# BKU.net
KiCad netlist of a schematic drawn in EAGLE
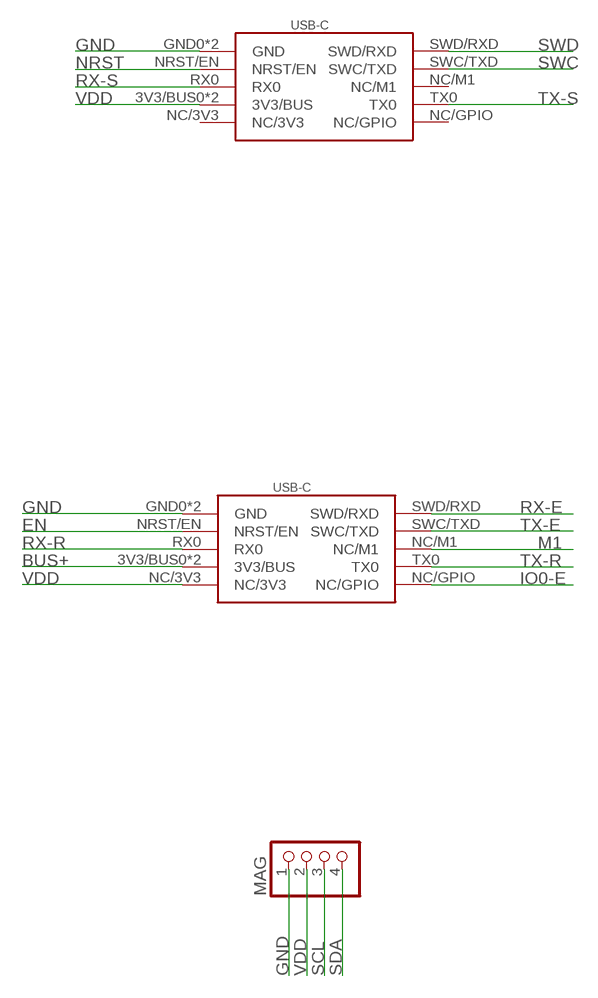
[diagram p0: schematic, sheet 1, part 1 of 2]
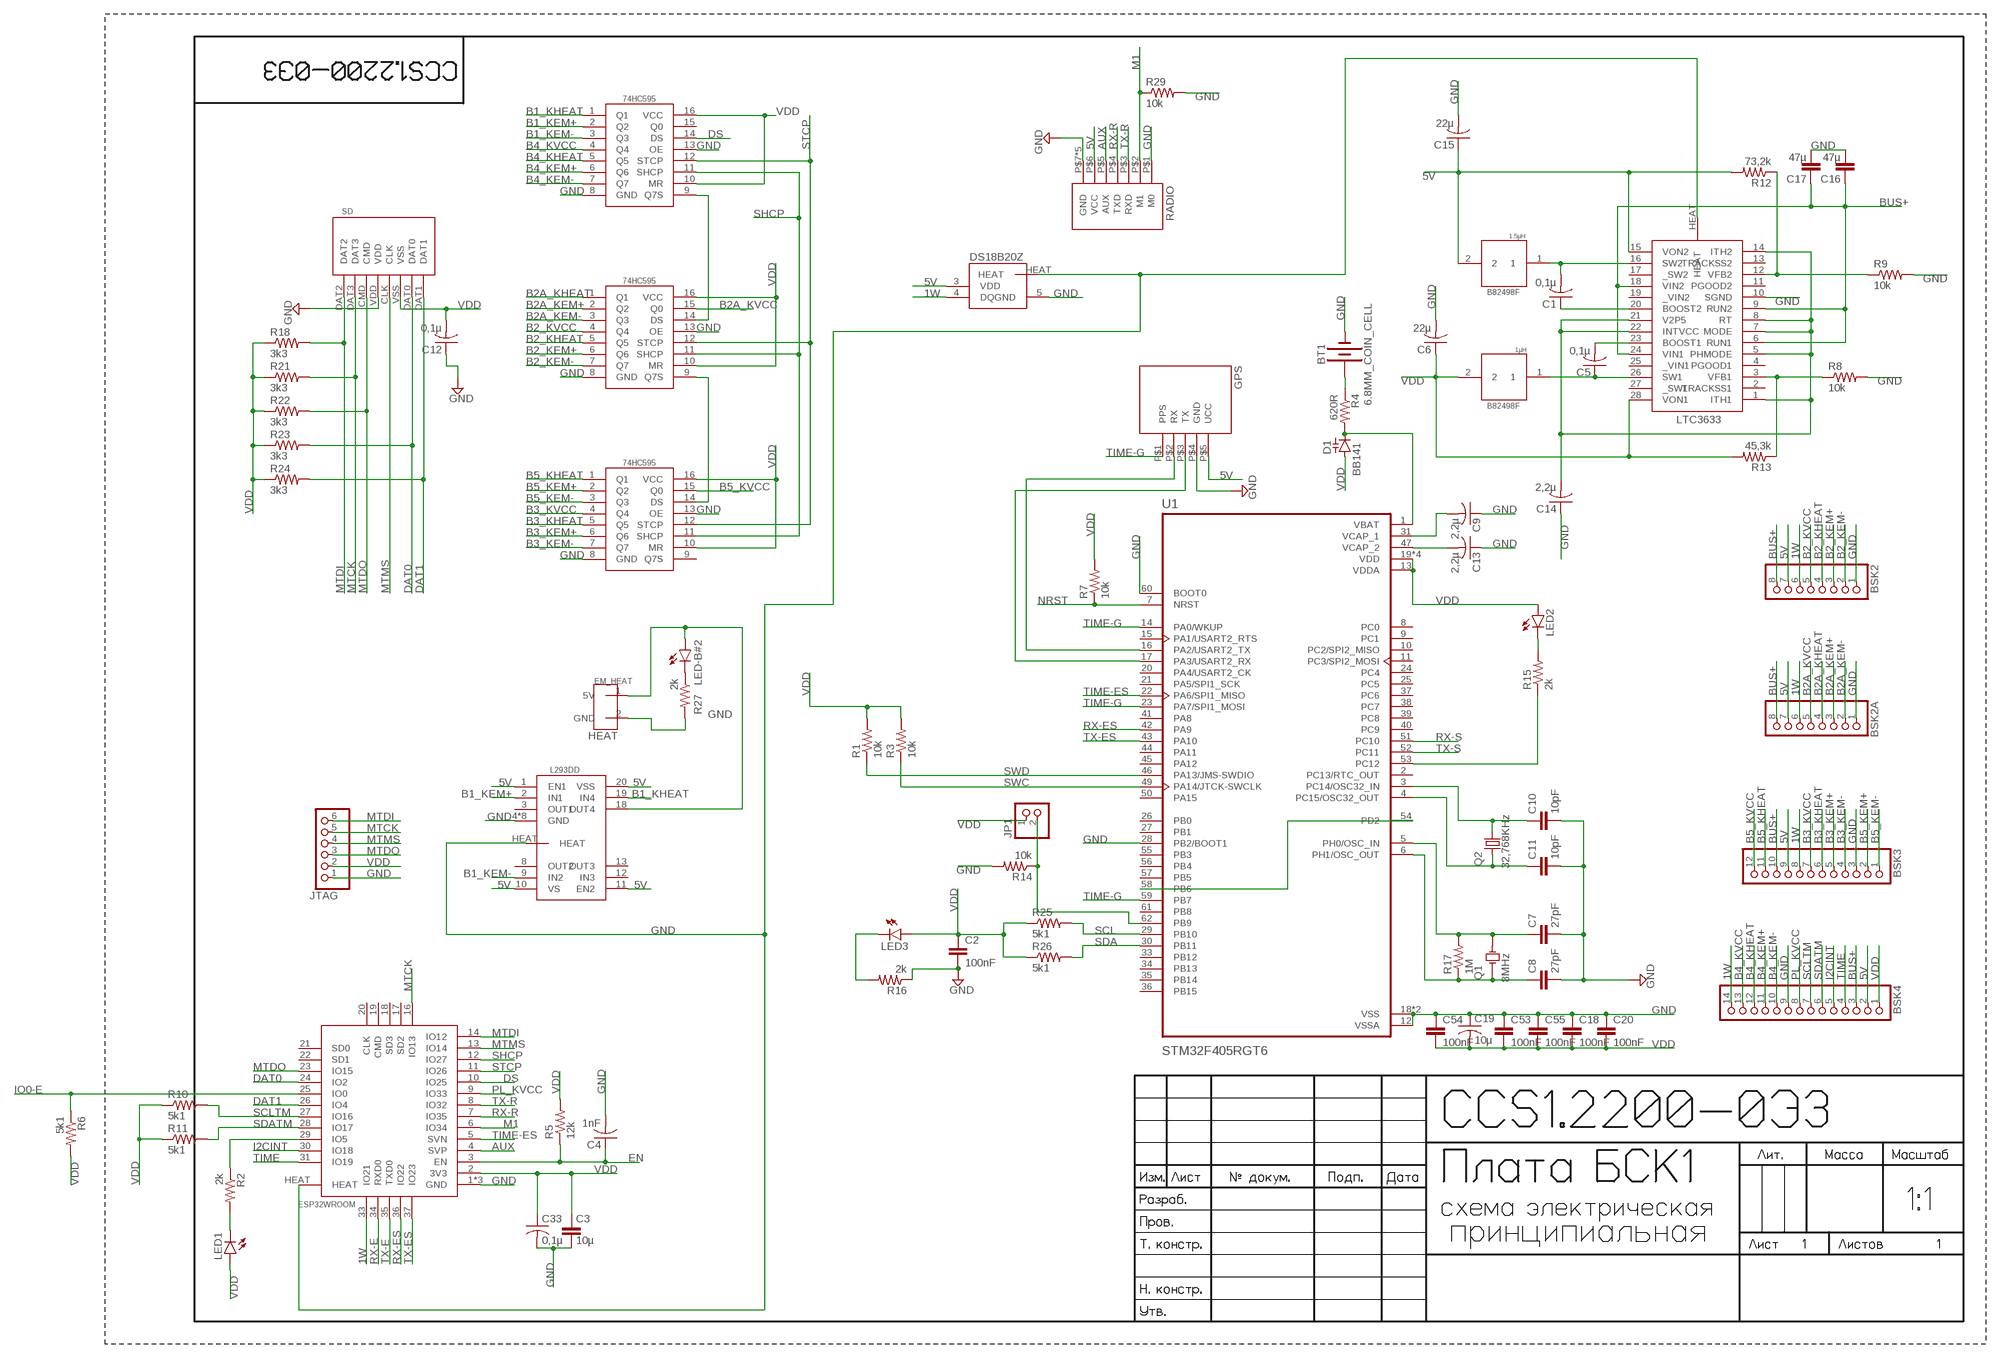
[diagram p1: schematic, sheet 1, part 2 of 2]

(export (version "E")
  (design (tool "Eeschema 10.0.6"))
  (components
    (comp (ref "BSK2")
      (value "PINHD-1X8")
      (footprint "eagle-import:1X08")
      (libsource (lib "eagle-import") (part "PINHD-1X8"))
    )
    (comp (ref "BSK2A")
      (value "PINHD-1X8")
      (footprint "eagle-import:1X08")
      (libsource (lib "eagle-import") (part "PINHD-1X8"))
    )
    (comp (ref "BSK3")
      (value "PINHD-1X12")
      (footprint "eagle-import:1X12")
      (libsource (lib "eagle-import") (part "PINHD-1X12"))
    )
    (comp (ref "BSK4")
      (value "PINHD-1X14")
      (footprint "eagle-import:1X14")
      (libsource (lib "eagle-import") (part "PINHD-1X14"))
    )
    (comp (ref "BT1")
      (value "6.8MM_COIN_CELL")
      (footprint "eagle-import:BATTCON-6.8MM")
      (libsource (lib "eagle-import") (part "BATTERY-6.8MM_SMD"))
    )
    (comp (ref "C1")
      (value "0,1µ")
      (footprint "eagle-import:C0603")
      (libsource (lib "eagle-import") (part "C-USC0603"))
    )
    (comp (ref "C2")
      (value "100nF")
      (footprint "eagle-import:C0603")
      (libsource (lib "eagle-import") (part "C-EUC0603"))
    )
    (comp (ref "C3")
      (value "10µ")
      (footprint "eagle-import:C1206")
      (libsource (lib "eagle-import") (part "C-EUC1206"))
    )
    (comp (ref "C4")
      (value "1nF")
      (footprint "eagle-import:C0603")
      (libsource (lib "eagle-import") (part "C-USC0603"))
    )
    (comp (ref "C5")
      (value "0,1µ")
      (footprint "eagle-import:C0603")
      (libsource (lib "eagle-import") (part "C-USC0603"))
    )
    (comp (ref "C6")
      (value "22µ")
      (footprint "eagle-import:C1206")
      (libsource (lib "eagle-import") (part "C-USC1206"))
    )
    (comp (ref "C7")
      (value "27pF")
      (footprint "eagle-import:C0603")
      (libsource (lib "eagle-import") (part "C-EUC0603"))
    )
    (comp (ref "C8")
      (value "27pF")
      (footprint "eagle-import:C0603")
      (libsource (lib "eagle-import") (part "C-EUC0603"))
    )
    (comp (ref "C9")
      (value "2,2µ")
      (footprint "eagle-import:C0603")
      (libsource (lib "eagle-import") (part "C-USC0603"))
    )
    (comp (ref "C10")
      (value "10pF")
      (footprint "eagle-import:C0603")
      (libsource (lib "eagle-import") (part "C-EUC0603"))
    )
    (comp (ref "C11")
      (value "10pF")
      (footprint "eagle-import:C0603")
      (libsource (lib "eagle-import") (part "C-EUC0603"))
    )
    (comp (ref "C12")
      (value "0,1µ")
      (footprint "eagle-import:C0603")
      (libsource (lib "eagle-import") (part "C-USC0603"))
    )
    (comp (ref "C13")
      (value "2,2µ")
      (footprint "eagle-import:C0603")
      (libsource (lib "eagle-import") (part "C-USC0603"))
    )
    (comp (ref "C14")
      (value "2,2µ")
      (footprint "eagle-import:C0603")
      (libsource (lib "eagle-import") (part "C-USC0603"))
    )
    (comp (ref "C15")
      (value "22µ")
      (footprint "eagle-import:C1206")
      (libsource (lib "eagle-import") (part "C-USC1206"))
    )
    (comp (ref "C16")
      (value "47µ")
      (footprint "eagle-import:C1210")
      (libsource (lib "eagle-import") (part "C-EUC1210"))
    )
    (comp (ref "C17")
      (value "47µ")
      (footprint "eagle-import:C1210")
      (libsource (lib "eagle-import") (part "C-EUC1210"))
    )
    (comp (ref "C18")
      (value "100nF")
      (footprint "eagle-import:C0603")
      (libsource (lib "eagle-import") (part "C-EUC0603"))
    )
    (comp (ref "C19")
      (value "10µ")
      (footprint "eagle-import:C1206")
      (libsource (lib "eagle-import") (part "C-USC1206"))
    )
    (comp (ref "C20")
      (value "100nF")
      (footprint "eagle-import:C0603")
      (libsource (lib "eagle-import") (part "C-EUC0603"))
    )
    (comp (ref "C33")
      (value "0,1µ")
      (footprint "eagle-import:C0603")
      (libsource (lib "eagle-import") (part "C-USC0603"))
    )
    (comp (ref "C53")
      (value "100nF")
      (footprint "eagle-import:C0603")
      (libsource (lib "eagle-import") (part "C-EUC0603"))
    )
    (comp (ref "C54")
      (value "100nF")
      (footprint "eagle-import:C0603")
      (libsource (lib "eagle-import") (part "C-EUC0603"))
    )
    (comp (ref "C55")
      (value "100nF")
      (footprint "eagle-import:C0603")
      (libsource (lib "eagle-import") (part "C-EUC0603"))
    )
    (comp (ref "D1")
      (value "BB141")
      (footprint "eagle-import:SOD523")
      (libsource (lib "eagle-import") (part "BB141"))
    )
    (comp (ref "GPS")
      (value "GPSNEO6M")
      (footprint "eagle-import:GPS-NEO6M")
      (libsource (lib "eagle-import") (part "GPSNEO6M"))
    )
    (comp (ref "JP1")
      (value "PINHD-1X2")
      (footprint "eagle-import:1X02")
      (libsource (lib "eagle-import") (part "PINHD-1X2"))
    )
    (comp (ref "JTAG")
      (value "PINHD-1X6")
      (footprint "eagle-import:1X06")
      (libsource (lib "eagle-import") (part "PINHD-1X6"))
    )
    (comp (ref "LED-B#2")
      (value "LEDCHIPLED_0603")
      (footprint "eagle-import:CHIPLED_0603")
      (libsource (lib "eagle-import") (part "LEDCHIPLED_0603"))
    )
    (comp (ref "LED1")
      (value "LEDCHIPLED_0603")
      (footprint "eagle-import:CHIPLED_0603")
      (libsource (lib "eagle-import") (part "LEDCHIPLED_0603"))
    )
    (comp (ref "LED2")
      (value "LEDCHIPLED_0603")
      (footprint "eagle-import:CHIPLED_0603")
      (libsource (lib "eagle-import") (part "LEDCHIPLED_0603"))
    )
    (comp (ref "LED3")
      (value "LEDCHIPLED_0603")
      (footprint "eagle-import:CHIPLED_0603")
      (libsource (lib "eagle-import") (part "LEDCHIPLED_0603"))
    )
    (comp (ref "MAG")
      (value "PINHD-1X4")
      (footprint "eagle-import:1X04")
      (libsource (lib "eagle-import") (part "PINHD-1X4"))
    )
    (comp (ref "Q1")
      (value "8MHz")
      (footprint "eagle-import:XTAL_9C-8.000MEEJ-T")
      (fields (field (name "MF") "TXC CORPORATION") (field (name "MP") "9C-8.000MEEJ-T"))
      (libsource (lib "eagle-import") (part "9C-8.000MEEJ-T"))
    )
    (comp (ref "Q2")
      (value "32,768KHz")
      (footprint "eagle-import:C005R")
      (libsource (lib "eagle-import") (part "C005R"))
    )
    (comp (ref "R1")
      (value "10k")
      (footprint "eagle-import:R0603")
      (libsource (lib "eagle-import") (part "R-US_R0603"))
    )
    (comp (ref "R2")
      (value "2k")
      (footprint "eagle-import:R0603")
      (libsource (lib "eagle-import") (part "R-US_R0603"))
    )
    (comp (ref "R3")
      (value "10k")
      (footprint "eagle-import:R0603")
      (libsource (lib "eagle-import") (part "R-US_R0603"))
    )
    (comp (ref "R4")
      (value "620R")
      (footprint "eagle-import:R0603")
      (libsource (lib "eagle-import") (part "R-US_R0603"))
    )
    (comp (ref "R5")
      (value "12k")
      (footprint "eagle-import:R0603")
      (libsource (lib "eagle-import") (part "R-US_R0603"))
    )
    (comp (ref "R6")
      (value "5k1")
      (footprint "eagle-import:R0603")
      (libsource (lib "eagle-import") (part "R-US_R0603"))
    )
    (comp (ref "R7")
      (value "10k")
      (footprint "eagle-import:R0603")
      (libsource (lib "eagle-import") (part "R-US_R0603"))
    )
    (comp (ref "R8")
      (value "10k")
      (footprint "eagle-import:R0603")
      (libsource (lib "eagle-import") (part "R-US_R0603"))
    )
    (comp (ref "R9")
      (value "10k")
      (footprint "eagle-import:R0603")
      (libsource (lib "eagle-import") (part "R-US_R0603"))
    )
    (comp (ref "R10")
      (value "5k1")
      (footprint "eagle-import:R0603")
      (libsource (lib "eagle-import") (part "R-US_R0603"))
    )
    (comp (ref "R11")
      (value "5k1")
      (footprint "eagle-import:R0603")
      (libsource (lib "eagle-import") (part "R-US_R0603"))
    )
    (comp (ref "R12")
      (value "73,2k")
      (footprint "eagle-import:R0603")
      (libsource (lib "eagle-import") (part "R-US_R0603"))
    )
    (comp (ref "R13")
      (value "45,3k")
      (footprint "eagle-import:R0603")
      (libsource (lib "eagle-import") (part "R-US_R0603"))
    )
    (comp (ref "R14")
      (value "10k")
      (footprint "eagle-import:R0603")
      (libsource (lib "eagle-import") (part "R-US_R0603"))
    )
    (comp (ref "R15")
      (value "2k")
      (footprint "eagle-import:R0603")
      (libsource (lib "eagle-import") (part "R-US_R0603"))
    )
    (comp (ref "R16")
      (value "2k")
      (footprint "eagle-import:R0603")
      (libsource (lib "eagle-import") (part "R-US_R0603"))
    )
    (comp (ref "R17")
      (value "1M")
      (footprint "eagle-import:R0603")
      (libsource (lib "eagle-import") (part "R-US_R0603"))
    )
    (comp (ref "R18")
      (value "3k3")
      (footprint "eagle-import:R0603")
      (libsource (lib "eagle-import") (part "R-US_R0603"))
    )
    (comp (ref "R21")
      (value "3k3")
      (footprint "eagle-import:R0603")
      (libsource (lib "eagle-import") (part "R-US_R0603"))
    )
    (comp (ref "R22")
      (value "3k3")
      (footprint "eagle-import:R0603")
      (libsource (lib "eagle-import") (part "R-US_R0603"))
    )
    (comp (ref "R23")
      (value "3k3")
      (footprint "eagle-import:R0603")
      (libsource (lib "eagle-import") (part "R-US_R0603"))
    )
    (comp (ref "R24")
      (value "3k3")
      (footprint "eagle-import:R0603")
      (libsource (lib "eagle-import") (part "R-US_R0603"))
    )
    (comp (ref "R25")
      (value "5k1")
      (footprint "eagle-import:R0603")
      (libsource (lib "eagle-import") (part "R-US_R0603"))
    )
    (comp (ref "R26")
      (value "5k1")
      (footprint "eagle-import:R0603")
      (libsource (lib "eagle-import") (part "R-US_R0603"))
    )
    (comp (ref "R27")
      (value "2k")
      (footprint "eagle-import:R0603")
      (libsource (lib "eagle-import") (part "R-US_R0603"))
    )
    (comp (ref "R29")
      (value "10k")
      (footprint "eagle-import:R0603")
      (libsource (lib "eagle-import") (part "R-US_R0603"))
    )
    (comp (ref "RADIO")
      (value "RADIO")
      (footprint "eagle-import:RADIO")
      (libsource (lib "eagle-import") (part "RADIO"))
    )
    (comp (ref "SD") (value "SD") (footprint "eagle-import:SD") (libsource (lib "eagle-import") (part "SD")))
    (comp (ref "U$4")
      (value "USB-C")
      (footprint "eagle-import:USB-C")
      (libsource (lib "eagle-import") (part "USB-C"))
    )
    (comp (ref "U$5")
      (value "DS18B20Z")
      (footprint "eagle-import:DS18B20Z")
      (libsource (lib "eagle-import") (part "DS18B20Z"))
    )
    (comp (ref "U$6")
      (value "USB-C")
      (footprint "eagle-import:USB-C")
      (libsource (lib "eagle-import") (part "USB-C"))
    )
    (comp (ref "U$7")
      (value "EM_HEAT")
      (footprint "eagle-import:EM_HEAT")
      (libsource (lib "eagle-import") (part "EM_HEAT"))
    )
    (comp (ref "U$8")
      (value "L293DD")
      (footprint "eagle-import:L293DD")
      (libsource (lib "eagle-import") (part "L293DD"))
    )
    (comp (ref "U$10")
      (value "LTC3633")
      (footprint "eagle-import:LTC3633")
      (libsource (lib "eagle-import") (part "LTC3633"))
    )
    (comp (ref "U$11")
      (value "1µH")
      (footprint "eagle-import:B82498F")
      (libsource (lib "eagle-import") (part "B82498F"))
    )
    (comp (ref "U$12")
      (value "B82498F")
      (footprint "eagle-import:B82498F")
      (libsource (lib "eagle-import") (part "B82498F"))
    )
    (comp (ref "U$13")
      (value "ESP32WROOM")
      (footprint "eagle-import:ESP32WROOM")
      (libsource (lib "eagle-import") (part "ESP32WROOM"))
    )
    (comp (ref "U$18")
      (value "74HC595")
      (footprint "eagle-import:74HC595")
      (libsource (lib "eagle-import") (part "74HC595"))
    )
    (comp (ref "U$19")
      (value "74HC595")
      (footprint "eagle-import:74HC595")
      (libsource (lib "eagle-import") (part "74HC595"))
    )
    (comp (ref "U$20")
      (value "74HC595")
      (footprint "eagle-import:74HC595")
      (libsource (lib "eagle-import") (part "74HC595"))
    )
    (comp (ref "U1")
      (value "STM32F405RGT6")
      (footprint "eagle-import:QFP50P1200X1200X160-64N")
      (fields (field (name "DIGI-KEY_PART_NUMBER") "497-11767-ND") (field (name "MF") "STMicroelectronics"))
      (libsource (lib "eagle-import") (part "STM32F405RGT6"))
    )
  )
  (nets
    (net (code "1") (name "/1W") (class "Default")
      (node (ref "BSK2") (pin "6") (pinfunction "6_6") (pintype "passive"))
      (node (ref "BSK2A") (pin "6") (pinfunction "6_6") (pintype "passive"))
      (node (ref "BSK3") (pin "8") (pinfunction "8_8") (pintype "passive"))
      (node (ref "BSK4") (pin "14") (pinfunction "14_14") (pintype "passive"))
      (node (ref "U$13") (pin "33") (pinfunction "IO21_33") (pintype "bidirectional"))
      (node (ref "U$5") (pin "4") (pinfunction "DQ_4") (pintype "bidirectional"))
    )
    (net (code "2") (name "/5V") (class "Default")
      (node (ref "BSK2") (pin "7") (pinfunction "7_7") (pintype "passive"))
      (node (ref "BSK2A") (pin "7") (pinfunction "7_7") (pintype "passive"))
      (node (ref "BSK3") (pin "9") (pinfunction "9_9") (pintype "passive"))
      (node (ref "BSK4") (pin "2") (pinfunction "2_2") (pintype "passive"))
      (node (ref "C15") (pin "1") (pinfunction "1_1") (pintype "passive"))
      (node (ref "GPS") (pin "P$5") (pinfunction "UCC_P$5") (pintype "bidirectional"))
      (node (ref "R12") (pin "2") (pinfunction "2_2") (pintype "passive"))
      (node (ref "RADIO") (pin "P$6") (pinfunction "VCC_P$6") (pintype "bidirectional"))
      (node (ref "U$10") (pin "15") (pinfunction "VON2_15") (pintype "bidirectional"))
      (node (ref "U$12") (pin "2") (pinfunction "2_2") (pintype "bidirectional"))
      (node (ref "U$5") (pin "3") (pinfunction "VDD_3") (pintype "bidirectional"))
      (node (ref "U$8") (pin "1") (pinfunction "EN1_1") (pintype "bidirectional"))
      (node (ref "U$8") (pin "10") (pinfunction "VS_10") (pintype "bidirectional"))
      (node (ref "U$8") (pin "11") (pinfunction "EN2_11") (pintype "bidirectional"))
      (node (ref "U$8") (pin "20") (pinfunction "VSS_20") (pintype "bidirectional"))
    )
    (net (code "3") (name "/AUX") (class "Default")
      (node (ref "RADIO") (pin "P$5") (pinfunction "AUX_P$5") (pintype "bidirectional"))
      (node (ref "U$13") (pin "4") (pinfunction "SVP_4") (pintype "bidirectional"))
    )
    (net (code "4") (name "/B1_KEM+") (class "Default")
      (node (ref "U$18") (pin "2") (pinfunction "Q2_2") (pintype "bidirectional"))
      (node (ref "U$8") (pin "2") (pinfunction "IN1_2") (pintype "bidirectional"))
    )
    (net (code "5") (name "/B1_KEM-") (class "Default")
      (node (ref "U$18") (pin "3") (pinfunction "Q3_3") (pintype "bidirectional"))
      (node (ref "U$8") (pin "9") (pinfunction "IN2_9") (pintype "bidirectional"))
    )
    (net (code "6") (name "/B1_KHEAT") (class "Default")
      (node (ref "U$18") (pin "1") (pinfunction "Q1_1") (pintype "bidirectional"))
      (node (ref "U$8") (pin "19") (pinfunction "IN4_19") (pintype "bidirectional"))
    )
    (net (code "7") (name "/B2A_KEM+") (class "Default")
      (node (ref "BSK2A") (pin "3") (pinfunction "3_3") (pintype "passive"))
      (node (ref "U$19") (pin "2") (pinfunction "Q2_2") (pintype "bidirectional"))
    )
    (net (code "8") (name "/B2A_KEM-") (class "Default")
      (node (ref "BSK2A") (pin "2") (pinfunction "2_2") (pintype "passive"))
      (node (ref "U$19") (pin "3") (pinfunction "Q3_3") (pintype "bidirectional"))
    )
    (net (code "9") (name "/B2A_KHEAT") (class "Default")
      (node (ref "BSK2A") (pin "4") (pinfunction "4_4") (pintype "passive"))
      (node (ref "U$19") (pin "1") (pinfunction "Q1_1") (pintype "bidirectional"))
    )
    (net (code "10") (name "/B2A_KVCC") (class "Default")
      (node (ref "BSK2A") (pin "5") (pinfunction "5_5") (pintype "passive"))
      (node (ref "U$19") (pin "15") (pinfunction "Q0_15") (pintype "bidirectional"))
    )
    (net (code "11") (name "/B2_KEM+") (class "Default")
      (node (ref "BSK2") (pin "3") (pinfunction "3_3") (pintype "passive"))
      (node (ref "U$19") (pin "6") (pinfunction "Q6_6") (pintype "bidirectional"))
    )
    (net (code "12") (name "/B2_KEM-") (class "Default")
      (node (ref "BSK2") (pin "2") (pinfunction "2_2") (pintype "passive"))
      (node (ref "U$19") (pin "7") (pinfunction "Q7_7") (pintype "bidirectional"))
    )
    (net (code "13") (name "/B2_KHEAT") (class "Default")
      (node (ref "BSK2") (pin "4") (pinfunction "4_4") (pintype "passive"))
      (node (ref "U$19") (pin "5") (pinfunction "Q5_5") (pintype "bidirectional"))
    )
    (net (code "14") (name "/B2_KVCC") (class "Default")
      (node (ref "BSK2") (pin "5") (pinfunction "5_5") (pintype "passive"))
      (node (ref "U$19") (pin "4") (pinfunction "Q4_4") (pintype "bidirectional"))
    )
    (net (code "15") (name "/B3_KEM+") (class "Default")
      (node (ref "BSK3") (pin "5") (pinfunction "5_5") (pintype "passive"))
      (node (ref "U$20") (pin "6") (pinfunction "Q6_6") (pintype "bidirectional"))
    )
    (net (code "16") (name "/B3_KEM-") (class "Default")
      (node (ref "BSK3") (pin "4") (pinfunction "4_4") (pintype "passive"))
      (node (ref "U$20") (pin "7") (pinfunction "Q7_7") (pintype "bidirectional"))
    )
    (net (code "17") (name "/B3_KHEAT") (class "Default")
      (node (ref "BSK3") (pin "6") (pinfunction "6_6") (pintype "passive"))
      (node (ref "U$20") (pin "5") (pinfunction "Q5_5") (pintype "bidirectional"))
    )
    (net (code "18") (name "/B3_KVCC") (class "Default")
      (node (ref "BSK3") (pin "7") (pinfunction "7_7") (pintype "passive"))
      (node (ref "U$20") (pin "4") (pinfunction "Q4_4") (pintype "bidirectional"))
    )
    (net (code "19") (name "/B4_KEM+") (class "Default")
      (node (ref "BSK4") (pin "11") (pinfunction "11_11") (pintype "passive"))
      (node (ref "U$18") (pin "6") (pinfunction "Q6_6") (pintype "bidirectional"))
    )
    (net (code "20") (name "/B4_KEM-") (class "Default")
      (node (ref "BSK4") (pin "10") (pinfunction "10_10") (pintype "passive"))
      (node (ref "U$18") (pin "7") (pinfunction "Q7_7") (pintype "bidirectional"))
    )
    (net (code "21") (name "/B4_KHEAT") (class "Default")
      (node (ref "BSK4") (pin "12") (pinfunction "12_12") (pintype "passive"))
      (node (ref "U$18") (pin "5") (pinfunction "Q5_5") (pintype "bidirectional"))
    )
    (net (code "22") (name "/B4_KVCC") (class "Default")
      (node (ref "BSK4") (pin "13") (pinfunction "13_13") (pintype "passive"))
      (node (ref "U$18") (pin "4") (pinfunction "Q4_4") (pintype "bidirectional"))
    )
    (net (code "23") (name "/B5_KEM+") (class "Default")
      (node (ref "BSK3") (pin "2") (pinfunction "2_2") (pintype "passive"))
      (node (ref "U$20") (pin "2") (pinfunction "Q2_2") (pintype "bidirectional"))
    )
    (net (code "24") (name "/B5_KEM-") (class "Default")
      (node (ref "BSK3") (pin "1") (pinfunction "1_1") (pintype "passive"))
      (node (ref "U$20") (pin "3") (pinfunction "Q3_3") (pintype "bidirectional"))
    )
    (net (code "25") (name "/B5_KHEAT") (class "Default")
      (node (ref "BSK3") (pin "11") (pinfunction "11_11") (pintype "passive"))
      (node (ref "U$20") (pin "1") (pinfunction "Q1_1") (pintype "bidirectional"))
    )
    (net (code "26") (name "/B5_KVCC") (class "Default")
      (node (ref "BSK3") (pin "12") (pinfunction "12_12") (pintype "passive"))
      (node (ref "U$20") (pin "15") (pinfunction "Q0_15") (pintype "bidirectional"))
    )
    (net (code "27") (name "/BUS+") (class "Default")
      (node (ref "BSK2") (pin "8") (pinfunction "8_8") (pintype "passive"))
      (node (ref "BSK2A") (pin "8") (pinfunction "8_8") (pintype "passive"))
      (node (ref "BSK3") (pin "10") (pinfunction "10_10") (pintype "passive"))
      (node (ref "BSK4") (pin "3") (pinfunction "3_3") (pintype "passive"))
      (node (ref "C16") (pin "1") (pinfunction "1_1") (pintype "passive"))
      (node (ref "C17") (pin "1") (pinfunction "1_1") (pintype "passive"))
      (node (ref "U$10") (pin "18") (pinfunction "VIN2_18") (pintype "bidirectional"))
      (node (ref "U$10") (pin "24") (pinfunction "VIN1_24") (pintype "bidirectional"))
      (node (ref "U$10") (pin "6") (pinfunction "RUN1_6") (pintype "bidirectional"))
      (node (ref "U$10") (pin "9") (pinfunction "RUN2_9") (pintype "bidirectional"))
      (node (ref "U$6") (pin "3V3/BUS0") (pinfunction "3V3/BUS_3V3/BUS0") (pintype "bidirectional"))
      (node (ref "U$6") (pin "3V3/BUS1") (pinfunction "3V3/BUS_3V3/BUS1") (pintype "bidirectional"))
    )
    (net (code "28") (name "/DAT0") (class "Default")
      (node (ref "R23") (pin "2") (pinfunction "2_2") (pintype "passive"))
      (node (ref "SD") (pin "DAT0") (pinfunction "DAT0_DAT0") (pintype "bidirectional"))
      (node (ref "U$13") (pin "24") (pinfunction "IO2_24") (pintype "bidirectional"))
    )
    (net (code "29") (name "/DAT1") (class "Default")
      (node (ref "R24") (pin "2") (pinfunction "2_2") (pintype "passive"))
      (node (ref "SD") (pin "DAT1") (pinfunction "DAT1_DAT1") (pintype "bidirectional"))
      (node (ref "U$13") (pin "26") (pinfunction "IO4_26") (pintype "bidirectional"))
    )
    (net (code "30") (name "/DS") (class "Default")
      (node (ref "U$13") (pin "10") (pinfunction "IO25_10") (pintype "bidirectional"))
      (node (ref "U$18") (pin "14") (pinfunction "DS_14") (pintype "bidirectional"))
    )
    (net (code "31") (name "/EN") (class "Default")
      (node (ref "C4") (pin "1") (pinfunction "1_1") (pintype "passive"))
      (node (ref "R5") (pin "1") (pinfunction "1_1") (pintype "passive"))
      (node (ref "U$13") (pin "3") (pinfunction "EN_3") (pintype "bidirectional"))
      (node (ref "U$6") (pin "NRST/EN") (pinfunction "NRST/EN_NRST/EN") (pintype "bidirectional"))
    )
    (net (code "32") (name "/I2CINT") (class "Default")
      (node (ref "BSK4") (pin "5") (pinfunction "5_5") (pintype "passive"))
      (node (ref "U$13") (pin "30") (pinfunction "IO18_30") (pintype "bidirectional"))
    )
    (net (code "33") (name "/IO0-E") (class "Default")
      (node (ref "R6") (pin "1") (pinfunction "1_1") (pintype "passive"))
      (node (ref "U$13") (pin "25") (pinfunction "IO0_25") (pintype "bidirectional"))
      (node (ref "U$6") (pin "NC/GPIO") (pinfunction "NC/GPIO_NC/GPIO") (pintype "bidirectional"))
    )
    (net (code "34") (name "/M1") (class "Default")
      (node (ref "R29") (pin "1") (pinfunction "1_1") (pintype "passive"))
      (node (ref "RADIO") (pin "P$2") (pinfunction "M1_P$2") (pintype "bidirectional"))
      (node (ref "U$13") (pin "6") (pinfunction "IO34_6") (pintype "bidirectional"))
      (node (ref "U$6") (pin "NC/M1") (pinfunction "NC/M1_NC/M1") (pintype "bidirectional"))
    )
    (net (code "35") (name "/MTCK") (class "Default")
      (node (ref "JTAG") (pin "5") (pinfunction "5_5") (pintype "passive"))
      (node (ref "R21") (pin "2") (pinfunction "2_2") (pintype "passive"))
      (node (ref "SD") (pin "DAT3") (pinfunction "DAT3_DAT3") (pintype "bidirectional"))
      (node (ref "U$13") (pin "16") (pinfunction "IO13_16") (pintype "bidirectional"))
    )
    (net (code "36") (name "/MTDI") (class "Default")
      (node (ref "JTAG") (pin "6") (pinfunction "6_6") (pintype "passive"))
      (node (ref "R18") (pin "2") (pinfunction "2_2") (pintype "passive"))
      (node (ref "SD") (pin "DAT2") (pinfunction "DAT2_DAT2") (pintype "bidirectional"))
      (node (ref "U$13") (pin "14") (pinfunction "IO12_14") (pintype "bidirectional"))
    )
    (net (code "37") (name "/MTDO") (class "Default")
      (node (ref "JTAG") (pin "3") (pinfunction "3_3") (pintype "passive"))
      (node (ref "R22") (pin "2") (pinfunction "2_2") (pintype "passive"))
      (node (ref "SD") (pin "CMD") (pinfunction "CMD_CMD") (pintype "bidirectional"))
      (node (ref "U$13") (pin "23") (pinfunction "IO15_23") (pintype "bidirectional"))
    )
    (net (code "38") (name "/MTMS") (class "Default")
      (node (ref "JTAG") (pin "4") (pinfunction "4_4") (pintype "passive"))
      (node (ref "SD") (pin "CLK") (pinfunction "CLK_CLK") (pintype "bidirectional"))
      (node (ref "U$13") (pin "13") (pinfunction "IO14_13") (pintype "bidirectional"))
    )
    (net (code "39") (name "/NRST") (class "Default")
      (node (ref "R7") (pin "1") (pinfunction "1_1") (pintype "passive"))
      (node (ref "U$4") (pin "NRST/EN") (pinfunction "NRST/EN_NRST/EN") (pintype "bidirectional"))
      (node (ref "U1") (pin "7") (pinfunction "NRST_7") (pintype "bidirectional"))
    )
    (net (code "40") (name "/PL_KVCC") (class "Default")
      (node (ref "BSK4") (pin "8") (pinfunction "8_8") (pintype "passive"))
      (node (ref "U$13") (pin "9") (pinfunction "IO33_9") (pintype "bidirectional"))
    )
    (net (code "41") (name "/RX-E") (class "Default")
      (node (ref "U$13") (pin "34") (pinfunction "RXD0_34") (pintype "bidirectional"))
      (node (ref "U$6") (pin "SWD/RXD") (pinfunction "SWD/RXD_SWD/RXD") (pintype "bidirectional"))
    )
    (net (code "42") (name "/RX-ES") (class "Default")
      (node (ref "U$13") (pin "36") (pinfunction "IO22_36") (pintype "bidirectional"))
      (node (ref "U1") (pin "42") (pinfunction "PA9_42") (pintype "bidirectional"))
    )
    (net (code "43") (name "/RX-R") (class "Default")
      (node (ref "RADIO") (pin "P$4") (pinfunction "TXD_P$4") (pintype "bidirectional"))
      (node (ref "U$13") (pin "7") (pinfunction "IO35_7") (pintype "bidirectional"))
      (node (ref "U$6") (pin "RX0") (pinfunction "RX0_RX0") (pintype "bidirectional"))
    )
    (net (code "44") (name "/RX-S") (class "Default")
      (node (ref "U$4") (pin "RX0") (pinfunction "RX0_RX0") (pintype "bidirectional"))
      (node (ref "U1") (pin "51") (pinfunction "PC10_51") (pintype "bidirectional"))
    )
    (net (code "45") (name "/SCL") (class "Default")
      (node (ref "MAG") (pin "3") (pinfunction "3_3") (pintype "passive"))
      (node (ref "R25") (pin "2") (pinfunction "2_2") (pintype "passive"))
      (node (ref "U1") (pin "29") (pinfunction "PB10_29") (pintype "bidirectional"))
    )
    (net (code "46") (name "/SCLTM") (class "Default")
      (node (ref "BSK4") (pin "7") (pinfunction "7_7") (pintype "passive"))
      (node (ref "R10") (pin "2") (pinfunction "2_2") (pintype "passive"))
      (node (ref "U$13") (pin "27") (pinfunction "IO16_27") (pintype "bidirectional"))
    )
    (net (code "47") (name "/SDA") (class "Default")
      (node (ref "MAG") (pin "4") (pinfunction "4_4") (pintype "passive"))
      (node (ref "R26") (pin "2") (pinfunction "2_2") (pintype "passive"))
      (node (ref "U1") (pin "30") (pinfunction "PB11_30") (pintype "bidirectional"))
    )
    (net (code "48") (name "/SDATM") (class "Default")
      (node (ref "BSK4") (pin "6") (pinfunction "6_6") (pintype "passive"))
      (node (ref "R11") (pin "2") (pinfunction "2_2") (pintype "passive"))
      (node (ref "U$13") (pin "28") (pinfunction "IO17_28") (pintype "bidirectional"))
    )
    (net (code "49") (name "/SHCP") (class "Default")
      (node (ref "U$13") (pin "12") (pinfunction "IO27_12") (pintype "bidirectional"))
      (node (ref "U$18") (pin "11") (pinfunction "SHCP_11") (pintype "bidirectional"))
      (node (ref "U$19") (pin "11") (pinfunction "SHCP_11") (pintype "bidirectional"))
      (node (ref "U$20") (pin "11") (pinfunction "SHCP_11") (pintype "bidirectional"))
    )
    (net (code "50") (name "/STCP") (class "Default")
      (node (ref "U$13") (pin "11") (pinfunction "IO26_11") (pintype "bidirectional"))
      (node (ref "U$18") (pin "12") (pinfunction "STCP_12") (pintype "bidirectional"))
      (node (ref "U$19") (pin "12") (pinfunction "STCP_12") (pintype "bidirectional"))
      (node (ref "U$20") (pin "12") (pinfunction "STCP_12") (pintype "bidirectional"))
    )
    (net (code "51") (name "/SWC") (class "Default")
      (node (ref "R3") (pin "1") (pinfunction "1_1") (pintype "passive"))
      (node (ref "U$4") (pin "SWC/TXD") (pinfunction "SWC/TXD_SWC/TXD") (pintype "bidirectional"))
      (node (ref "U1") (pin "49") (pinfunction "PA14/JTCK-SWCLK_49") (pintype "bidirectional"))
    )
    (net (code "52") (name "/SWD") (class "Default")
      (node (ref "R1") (pin "1") (pinfunction "1_1") (pintype "passive"))
      (node (ref "U$4") (pin "SWD/RXD") (pinfunction "SWD/RXD_SWD/RXD") (pintype "bidirectional"))
      (node (ref "U1") (pin "46") (pinfunction "PA13/JMS-SWDIO_46") (pintype "bidirectional"))
    )
    (net (code "53") (name "/TIME") (class "Default")
      (node (ref "BSK4") (pin "4") (pinfunction "4_4") (pintype "passive"))
      (node (ref "U$13") (pin "31") (pinfunction "IO19_31") (pintype "bidirectional"))
    )
    (net (code "54") (name "/TIME-ES") (class "Default")
      (node (ref "U$13") (pin "5") (pinfunction "SVN_5") (pintype "bidirectional"))
      (node (ref "U1") (pin "22") (pinfunction "PA6/SPI1_MISO_22") (pintype "bidirectional"))
    )
    (net (code "55") (name "/TIME-G") (class "Default")
      (node (ref "GPS") (pin "P$1") (pinfunction "PPS_P$1") (pintype "bidirectional"))
      (node (ref "U1") (pin "14") (pinfunction "PA0/WKUP_14") (pintype "bidirectional"))
      (node (ref "U1") (pin "23") (pinfunction "PA7/SPI1_MOSI_23") (pintype "bidirectional"))
      (node (ref "U1") (pin "59") (pinfunction "PB7_59") (pintype "bidirectional"))
    )
    (net (code "56") (name "/TX-E") (class "Default")
      (node (ref "U$13") (pin "35") (pinfunction "TXD0_35") (pintype "bidirectional"))
      (node (ref "U$6") (pin "SWC/TXD") (pinfunction "SWC/TXD_SWC/TXD") (pintype "bidirectional"))
    )
    (net (code "57") (name "/TX-ES") (class "Default")
      (node (ref "U$13") (pin "37") (pinfunction "IO23_37") (pintype "bidirectional"))
      (node (ref "U1") (pin "43") (pinfunction "PA10_43") (pintype "bidirectional"))
    )
    (net (code "58") (name "/TX-R") (class "Default")
      (node (ref "RADIO") (pin "P$3") (pinfunction "RXD_P$3") (pintype "bidirectional"))
      (node (ref "U$13") (pin "8") (pinfunction "IO32_8") (pintype "bidirectional"))
      (node (ref "U$6") (pin "TX0") (pinfunction "TX0_TX0") (pintype "bidirectional"))
    )
    (net (code "59") (name "/TX-S") (class "Default")
      (node (ref "U$4") (pin "TX0") (pinfunction "TX0_TX0") (pintype "bidirectional"))
      (node (ref "U1") (pin "52") (pinfunction "PC11_52") (pintype "bidirectional"))
    )
    (net (code "60") (name "/VDD") (class "Default")
      (node (ref "BSK4") (pin "1") (pinfunction "1_1") (pintype "passive"))
      (node (ref "C12") (pin "2") (pinfunction "2_2") (pintype "passive"))
      (node (ref "C18") (pin "2") (pinfunction "2_2") (pintype "passive"))
      (node (ref "C19") (pin "2") (pinfunction "2_2") (pintype "passive"))
      (node (ref "C2") (pin "1") (pinfunction "1_1") (pintype "passive"))
      (node (ref "C20") (pin "2") (pinfunction "2_2") (pintype "passive"))
      (node (ref "C3") (pin "1") (pinfunction "1_1") (pintype "passive"))
      (node (ref "C33") (pin "1") (pinfunction "1_1") (pintype "passive"))
      (node (ref "C53") (pin "2") (pinfunction "2_2") (pintype "passive"))
      (node (ref "C54") (pin "2") (pinfunction "2_2") (pintype "passive"))
      (node (ref "C55") (pin "2") (pinfunction "2_2") (pintype "passive"))
      (node (ref "C6") (pin "1") (pinfunction "1_1") (pintype "passive"))
      (node (ref "D1") (pin "A") (pinfunction "A_A") (pintype "passive"))
      (node (ref "JP1") (pin "1") (pinfunction "1_1") (pintype "passive"))
      (node (ref "JTAG") (pin "2") (pinfunction "2_2") (pintype "passive"))
      (node (ref "LED1") (pin "A") (pinfunction "A_A") (pintype "passive"))
      (node (ref "LED2") (pin "A") (pinfunction "A_A") (pintype "passive"))
      (node (ref "LED3") (pin "A") (pinfunction "A_A") (pintype "passive"))
      (node (ref "MAG") (pin "2") (pinfunction "2_2") (pintype "passive"))
      (node (ref "R1") (pin "2") (pinfunction "2_2") (pintype "passive"))
      (node (ref "R10") (pin "1") (pinfunction "1_1") (pintype "passive"))
      (node (ref "R11") (pin "1") (pinfunction "1_1") (pintype "passive"))
      (node (ref "R13") (pin "2") (pinfunction "2_2") (pintype "passive"))
      (node (ref "R18") (pin "1") (pinfunction "1_1") (pintype "passive"))
      (node (ref "R21") (pin "1") (pinfunction "1_1") (pintype "passive"))
      (node (ref "R22") (pin "1") (pinfunction "1_1") (pintype "passive"))
      (node (ref "R23") (pin "1") (pinfunction "1_1") (pintype "passive"))
      (node (ref "R24") (pin "1") (pinfunction "1_1") (pintype "passive"))
      (node (ref "R25") (pin "1") (pinfunction "1_1") (pintype "passive"))
      (node (ref "R26") (pin "1") (pinfunction "1_1") (pintype "passive"))
      (node (ref "R3") (pin "2") (pinfunction "2_2") (pintype "passive"))
      (node (ref "R5") (pin "2") (pinfunction "2_2") (pintype "passive"))
      (node (ref "R6") (pin "2") (pinfunction "2_2") (pintype "passive"))
      (node (ref "R7") (pin "2") (pinfunction "2_2") (pintype "passive"))
      (node (ref "SD") (pin "VSS") (pinfunction "VSS_VSS") (pintype "bidirectional"))
      (node (ref "U$10") (pin "28") (pinfunction "VON1_28") (pintype "bidirectional"))
      (node (ref "U$11") (pin "2") (pinfunction "2_2") (pintype "bidirectional"))
      (node (ref "U$13") (pin "2") (pinfunction "3V3_2") (pintype "bidirectional"))
      (node (ref "U$18") (pin "10") (pinfunction "MR_10") (pintype "bidirectional"))
      (node (ref "U$18") (pin "16") (pinfunction "VCC_16") (pintype "bidirectional"))
      (node (ref "U$19") (pin "10") (pinfunction "MR_10") (pintype "bidirectional"))
      (node (ref "U$19") (pin "16") (pinfunction "VCC_16") (pintype "bidirectional"))
      (node (ref "U$20") (pin "10") (pinfunction "MR_10") (pintype "bidirectional"))
      (node (ref "U$20") (pin "16") (pinfunction "VCC_16") (pintype "bidirectional"))
      (node (ref "U$4") (pin "3V3/BUS0") (pinfunction "3V3/BUS_3V3/BUS0") (pintype "bidirectional"))
      (node (ref "U$4") (pin "3V3/BUS1") (pinfunction "3V3/BUS_3V3/BUS1") (pintype "bidirectional"))
      (node (ref "U$6") (pin "NC/3V3") (pinfunction "NC/3V3_NC/3V3") (pintype "bidirectional"))
      (node (ref "U1") (pin "13") (pinfunction "VDDA_13") (pintype "power_in"))
      (node (ref "U1") (pin "19") (pinfunction "VDD_19") (pintype "power_in"))
      (node (ref "U1") (pin "32") (pinfunction "VDD_32") (pintype "power_in"))
      (node (ref "U1") (pin "48") (pinfunction "VDD_48") (pintype "power_in"))
      (node (ref "U1") (pin "64") (pinfunction "VDD_64") (pintype "power_in"))
    )
    (net (code "61") (name "GND") (class "Default")
      (node (ref "BSK2") (pin "1") (pinfunction "1_1") (pintype "passive"))
      (node (ref "BSK2A") (pin "1") (pinfunction "1_1") (pintype "passive"))
      (node (ref "BSK3") (pin "3") (pinfunction "3_3") (pintype "passive"))
      (node (ref "BSK4") (pin "9") (pinfunction "9_9") (pintype "passive"))
      (node (ref "BT1") (pin "-") (pinfunction "-_-") (pintype "power_in"))
      (node (ref "C10") (pin "2") (pinfunction "2_2") (pintype "passive"))
      (node (ref "C11") (pin "2") (pinfunction "2_2") (pintype "passive"))
      (node (ref "C12") (pin "1") (pinfunction "1_1") (pintype "passive"))
      (node (ref "C13") (pin "1") (pinfunction "1_1") (pintype "passive"))
      (node (ref "C14") (pin "1") (pinfunction "1_1") (pintype "passive"))
      (node (ref "C15") (pin "2") (pinfunction "2_2") (pintype "passive"))
      (node (ref "C16") (pin "2") (pinfunction "2_2") (pintype "passive"))
      (node (ref "C17") (pin "2") (pinfunction "2_2") (pintype "passive"))
      (node (ref "C18") (pin "1") (pinfunction "1_1") (pintype "passive"))
      (node (ref "C19") (pin "1") (pinfunction "1_1") (pintype "passive"))
      (node (ref "C2") (pin "2") (pinfunction "2_2") (pintype "passive"))
      (node (ref "C20") (pin "1") (pinfunction "1_1") (pintype "passive"))
      (node (ref "C3") (pin "2") (pinfunction "2_2") (pintype "passive"))
      (node (ref "C33") (pin "2") (pinfunction "2_2") (pintype "passive"))
      (node (ref "C4") (pin "2") (pinfunction "2_2") (pintype "passive"))
      (node (ref "C53") (pin "1") (pinfunction "1_1") (pintype "passive"))
      (node (ref "C54") (pin "1") (pinfunction "1_1") (pintype "passive"))
      (node (ref "C55") (pin "1") (pinfunction "1_1") (pintype "passive"))
      (node (ref "C6") (pin "2") (pinfunction "2_2") (pintype "passive"))
      (node (ref "C7") (pin "2") (pinfunction "2_2") (pintype "passive"))
      (node (ref "C8") (pin "2") (pinfunction "2_2") (pintype "passive"))
      (node (ref "C9") (pin "1") (pinfunction "1_1") (pintype "passive"))
      (node (ref "GPS") (pin "P$4") (pinfunction "GND_P$4") (pintype "bidirectional"))
      (node (ref "JTAG") (pin "1") (pinfunction "1_1") (pintype "passive"))
      (node (ref "MAG") (pin "1") (pinfunction "1_1") (pintype "passive"))
      (node (ref "R14") (pin "2") (pinfunction "2_2") (pintype "passive"))
      (node (ref "R16") (pin "1") (pinfunction "1_1") (pintype "passive"))
      (node (ref "R27") (pin "2") (pinfunction "2_2") (pintype "passive"))
      (node (ref "R29") (pin "2") (pinfunction "2_2") (pintype "passive"))
      (node (ref "R8") (pin "2") (pinfunction "2_2") (pintype "passive"))
      (node (ref "R9") (pin "2") (pinfunction "2_2") (pintype "passive"))
      (node (ref "RADIO") (pin "P$1") (pinfunction "M0_P$1") (pintype "bidirectional"))
      (node (ref "RADIO") (pin "P$15") (pinfunction "GND_P$15") (pintype "bidirectional"))
      (node (ref "RADIO") (pin "P$16") (pinfunction "GND_P$16") (pintype "bidirectional"))
      (node (ref "RADIO") (pin "P$17") (pinfunction "GND_P$17") (pintype "bidirectional"))
      (node (ref "RADIO") (pin "P$7") (pinfunction "GND_P$7") (pintype "bidirectional"))
      (node (ref "RADIO") (pin "P$9") (pinfunction "GND_P$9") (pintype "bidirectional"))
      (node (ref "SD") (pin "VDD") (pinfunction "VDD_VDD") (pintype "bidirectional"))
      (node (ref "U$10") (pin "10") (pinfunction "SGND_10") (pintype "bidirectional"))
      (node (ref "U$10") (pin "HEAT") (pinfunction "HEAT_HEAT") (pintype "bidirectional"))
      (node (ref "U$13") (pin "1") (pinfunction "GND_1") (pintype "bidirectional"))
      (node (ref "U$13") (pin "15") (pinfunction "GND_15") (pintype "bidirectional"))
      (node (ref "U$13") (pin "38") (pinfunction "GND_38") (pintype "bidirectional"))
      (node (ref "U$13") (pin "HEAT") (pinfunction "HEAT_HEAT") (pintype "bidirectional"))
      (node (ref "U$18") (pin "13") (pinfunction "OE_13") (pintype "bidirectional"))
      (node (ref "U$18") (pin "8") (pinfunction "GND_8") (pintype "bidirectional"))
      (node (ref "U$19") (pin "13") (pinfunction "OE_13") (pintype "bidirectional"))
      (node (ref "U$19") (pin "8") (pinfunction "GND_8") (pintype "bidirectional"))
      (node (ref "U$20") (pin "13") (pinfunction "OE_13") (pintype "bidirectional"))
      (node (ref "U$20") (pin "8") (pinfunction "GND_8") (pintype "bidirectional"))
      (node (ref "U$4") (pin "GND0") (pinfunction "GND_GND0") (pintype "bidirectional"))
      (node (ref "U$4") (pin "GND1") (pinfunction "GND_GND1") (pintype "bidirectional"))
      (node (ref "U$5") (pin "5") (pinfunction "GND_5") (pintype "bidirectional"))
      (node (ref "U$5") (pin "HEAT") (pinfunction "HEAT_HEAT") (pintype "bidirectional"))
      (node (ref "U$6") (pin "GND0") (pinfunction "GND_GND0") (pintype "bidirectional"))
      (node (ref "U$6") (pin "GND1") (pinfunction "GND_GND1") (pintype "bidirectional"))
      (node (ref "U$7") (pin "2") (pinfunction "GND_2") (pintype "bidirectional"))
      (node (ref "U$8") (pin "14") (pinfunction "GND_14") (pintype "bidirectional"))
      (node (ref "U$8") (pin "15") (pinfunction "GND_15") (pintype "bidirectional"))
      (node (ref "U$8") (pin "16") (pinfunction "GND_16") (pintype "bidirectional"))
      (node (ref "U$8") (pin "17") (pinfunction "GND_17") (pintype "bidirectional"))
      (node (ref "U$8") (pin "4") (pinfunction "GND_4") (pintype "bidirectional"))
      (node (ref "U$8") (pin "5") (pinfunction "GND_5") (pintype "bidirectional"))
      (node (ref "U$8") (pin "6") (pinfunction "GND_6") (pintype "bidirectional"))
      (node (ref "U$8") (pin "7") (pinfunction "GND_7") (pintype "bidirectional"))
      (node (ref "U$8") (pin "HEAT") (pinfunction "HEAT_HEAT") (pintype "bidirectional"))
      (node (ref "U1") (pin "12") (pinfunction "VSSA_12") (pintype "power_in"))
      (node (ref "U1") (pin "18") (pinfunction "VSS_18") (pintype "power_in"))
      (node (ref "U1") (pin "28") (pinfunction "PB2/BOOT1_28") (pintype "bidirectional"))
      (node (ref "U1") (pin "60") (pinfunction "BOOT0_60") (pintype "bidirectional"))
      (node (ref "U1") (pin "63") (pinfunction "VSS_63") (pintype "power_in"))
    )
    (net (code "62") (name "Net-(BT1-Pad+)") (class "Default")
      (node (ref "BT1") (pin "+") (pinfunction "+_+") (pintype "power_in"))
      (node (ref "R4") (pin "1") (pinfunction "1_1") (pintype "passive"))
    )
    (net (code "63") (name "Net-(GPS-RX)") (class "Default")
      (node (ref "GPS") (pin "P$2") (pinfunction "RX_P$2") (pintype "bidirectional"))
      (node (ref "U1") (pin "16") (pinfunction "PA2/USART2_TX_16") (pintype "bidirectional"))
    )
    (net (code "64") (name "Net-(GPS-TX)") (class "Default")
      (node (ref "GPS") (pin "P$3") (pinfunction "TX_P$3") (pintype "bidirectional"))
      (node (ref "U1") (pin "17") (pinfunction "PA3/USART2_RX_17") (pintype "bidirectional"))
    )
    (net (code "65") (name "Net-(LED-B#2-PadC)") (class "Default")
      (node (ref "LED-B#2") (pin "C") (pinfunction "C_C") (pintype "passive"))
      (node (ref "R27") (pin "1") (pinfunction "1_1") (pintype "passive"))
    )
    (net (code "66") (name "Net-(LED1-PadC)") (class "Default")
      (node (ref "LED1") (pin "C") (pinfunction "C_C") (pintype "passive"))
      (node (ref "R2") (pin "2") (pinfunction "2_2") (pintype "passive"))
    )
    (net (code "67") (name "Net-(LED2-PadC)") (class "Default")
      (node (ref "LED2") (pin "C") (pinfunction "C_C") (pintype "passive"))
      (node (ref "R15") (pin "2") (pinfunction "2_2") (pintype "passive"))
    )
    (net (code "68") (name "Net-(LED3-PadC)") (class "Default")
      (node (ref "LED3") (pin "C") (pinfunction "C_C") (pintype "passive"))
      (node (ref "R16") (pin "2") (pinfunction "2_2") (pintype "passive"))
    )
    (net (code "69") (name "Net-(Q2-1)") (class "Default")
      (node (ref "C11") (pin "1") (pinfunction "1_1") (pintype "passive"))
      (node (ref "Q2") (pin "P$1") (pinfunction "1_P$1") (pintype "passive"))
      (node (ref "U1") (pin "4") (pinfunction "PC15/OSC32_OUT_4") (pintype "bidirectional"))
    )
    (net (code "70") (name "Net-(Q2-2)") (class "Default")
      (node (ref "C10") (pin "1") (pinfunction "1_1") (pintype "passive"))
      (node (ref "Q2") (pin "P$2") (pinfunction "2_P$2") (pintype "passive"))
      (node (ref "U1") (pin "3") (pinfunction "PC14/OSC32_IN_3") (pintype "bidirectional"))
    )
    (net (code "71") (name "Net-(U$7-5V)") (class "Default")
      (node (ref "LED-B#2") (pin "A") (pinfunction "A_A") (pintype "passive"))
      (node (ref "U$7") (pin "1") (pinfunction "5V_1") (pintype "bidirectional"))
      (node (ref "U$8") (pin "18") (pinfunction "OUT4_18") (pintype "bidirectional"))
    )
    (net (code "72") (name "Net-(U$10-BOOST1)") (class "Default")
      (node (ref "C5") (pin "2") (pinfunction "2_2") (pintype "passive"))
      (node (ref "U$10") (pin "23") (pinfunction "BOOST1_23") (pintype "bidirectional"))
    )
    (net (code "73") (name "Net-(U$10-BOOST2)") (class "Default")
      (node (ref "C1") (pin "1") (pinfunction "1_1") (pintype "passive"))
      (node (ref "U$10") (pin "20") (pinfunction "BOOST2_20") (pintype "bidirectional"))
    )
    (net (code "74") (name "Net-(U$10-INTVCC)") (class "Default")
      (node (ref "C14") (pin "2") (pinfunction "2_2") (pintype "passive"))
      (node (ref "U$10") (pin "1") (pinfunction "ITH1_1") (pintype "bidirectional"))
      (node (ref "U$10") (pin "14") (pinfunction "ITH2_14") (pintype "bidirectional"))
      (node (ref "U$10") (pin "21") (pinfunction "V2P5_21") (pintype "bidirectional"))
      (node (ref "U$10") (pin "22") (pinfunction "INTVCC_22") (pintype "bidirectional"))
      (node (ref "U$10") (pin "5") (pinfunction "PHMODE_5") (pintype "bidirectional"))
      (node (ref "U$10") (pin "7") (pinfunction "MODE_7") (pintype "bidirectional"))
      (node (ref "U$10") (pin "8") (pinfunction "RT_8") (pintype "bidirectional"))
    )
    (net (code "75") (name "Net-(U$10-SW1)") (class "Default")
      (node (ref "C5") (pin "1") (pinfunction "1_1") (pintype "passive"))
      (node (ref "U$10") (pin "26") (pinfunction "SW1_26") (pintype "bidirectional"))
      (node (ref "U$11") (pin "1") (pinfunction "1_1") (pintype "bidirectional"))
    )
    (net (code "76") (name "Net-(U$10-SW2)") (class "Default")
      (node (ref "C1") (pin "2") (pinfunction "2_2") (pintype "passive"))
      (node (ref "U$10") (pin "16") (pinfunction "SW2_16") (pintype "bidirectional"))
      (node (ref "U$12") (pin "1") (pinfunction "1_1") (pintype "bidirectional"))
    )
    (net (code "77") (name "Net-(U$10-VFB1)") (class "Default")
      (node (ref "R13") (pin "1") (pinfunction "1_1") (pintype "passive"))
      (node (ref "R8") (pin "1") (pinfunction "1_1") (pintype "passive"))
      (node (ref "U$10") (pin "3") (pinfunction "VFB1_3") (pintype "bidirectional"))
    )
    (net (code "78") (name "Net-(U$10-VFB2)") (class "Default")
      (node (ref "R12") (pin "1") (pinfunction "1_1") (pintype "passive"))
      (node (ref "R9") (pin "1") (pinfunction "1_1") (pintype "passive"))
      (node (ref "U$10") (pin "12") (pinfunction "VFB2_12") (pintype "bidirectional"))
    )
    (net (code "79") (name "Net-(U$13-IO5)") (class "Default")
      (node (ref "R2") (pin "1") (pinfunction "1_1") (pintype "passive"))
      (node (ref "U$13") (pin "29") (pinfunction "IO5_29") (pintype "bidirectional"))
    )
    (net (code "80") (name "Net-(U$18-Q7S)") (class "Default")
      (node (ref "U$18") (pin "9") (pinfunction "Q7S_9") (pintype "bidirectional"))
      (node (ref "U$19") (pin "14") (pinfunction "DS_14") (pintype "bidirectional"))
    )
    (net (code "81") (name "Net-(U$19-Q7S)") (class "Default")
      (node (ref "U$19") (pin "9") (pinfunction "Q7S_9") (pintype "bidirectional"))
      (node (ref "U$20") (pin "14") (pinfunction "DS_14") (pintype "bidirectional"))
    )
    (net (code "82") (name "Net-(U1-PB6)") (class "Default")
      (node (ref "U1") (pin "54") (pinfunction "PD2_54") (pintype "bidirectional"))
      (node (ref "U1") (pin "58") (pinfunction "PB6_58") (pintype "bidirectional"))
    )
    (net (code "83") (name "Net-(U1-PB9)") (class "Default")
      (node (ref "JP1") (pin "2") (pinfunction "2_2") (pintype "passive"))
      (node (ref "R14") (pin "1") (pinfunction "1_1") (pintype "passive"))
      (node (ref "U1") (pin "62") (pinfunction "PB9_62") (pintype "bidirectional"))
    )
    (net (code "84") (name "Net-(U1-PC12)") (class "Default")
      (node (ref "R15") (pin "1") (pinfunction "1_1") (pintype "passive"))
      (node (ref "U1") (pin "53") (pinfunction "PC12_53") (pintype "bidirectional"))
    )
    (net (code "85") (name "Net-(U1-PH0{slash}OSC_IN)") (class "Default")
      (node (ref "C7") (pin "1") (pinfunction "1_1") (pintype "passive"))
      (node (ref "Q1") (pin "2") (pinfunction "2_2") (pintype "passive"))
      (node (ref "R17") (pin "2") (pinfunction "2_2") (pintype "passive"))
      (node (ref "U1") (pin "5") (pinfunction "PH0/OSC_IN_5") (pintype "bidirectional"))
    )
    (net (code "86") (name "Net-(U1-PH1{slash}OSC_OUT)") (class "Default")
      (node (ref "C8") (pin "1") (pinfunction "1_1") (pintype "passive"))
      (node (ref "Q1") (pin "1") (pinfunction "1_1") (pintype "passive"))
      (node (ref "R17") (pin "1") (pinfunction "1_1") (pintype "passive"))
      (node (ref "U1") (pin "6") (pinfunction "PH1/OSC_OUT_6") (pintype "bidirectional"))
    )
    (net (code "87") (name "Net-(U1-VBAT)") (class "Default")
      (node (ref "D1") (pin "C") (pinfunction "C_C") (pintype "passive"))
      (node (ref "R4") (pin "2") (pinfunction "2_2") (pintype "passive"))
      (node (ref "U1") (pin "1") (pinfunction "VBAT_1") (pintype "power_in"))
    )
    (net (code "88") (name "Net-(U1-VCAP_1)") (class "Default")
      (node (ref "C9") (pin "2") (pinfunction "2_2") (pintype "passive"))
      (node (ref "U1") (pin "31") (pinfunction "VCAP_1_31") (pintype "power_in"))
    )
    (net (code "89") (name "Net-(U1-VCAP_2)") (class "Default")
      (node (ref "C13") (pin "2") (pinfunction "2_2") (pintype "passive"))
      (node (ref "U1") (pin "47") (pinfunction "VCAP_2_47") (pintype "power_in"))
    )
    (net (code "90") (name "unconnected-(U$4-PadNC{slash}3V3)") (class "Default")
      (node (ref "U$4") (pin "NC/3V3") (pinfunction "NC/3V3_NC/3V3") (pintype "bidirectional"))
    )
    (net (code "91") (name "unconnected-(U$4-PadNC{slash}GPIO)") (class "Default")
      (node (ref "U$4") (pin "NC/GPIO") (pinfunction "NC/GPIO_NC/GPIO") (pintype "bidirectional"))
    )
    (net (code "92") (name "unconnected-(U$4-PadNC{slash}M1)") (class "Default")
      (node (ref "U$4") (pin "NC/M1") (pinfunction "NC/M1_NC/M1") (pintype "bidirectional"))
    )
    (net (code "93") (name "unconnected-(U$8-IN3-Pad12)") (class "Default")
      (node (ref "U$8") (pin "12") (pinfunction "IN3_12") (pintype "bidirectional"))
    )
    (net (code "94") (name "unconnected-(U$8-OUT1-Pad3)") (class "Default")
      (node (ref "U$8") (pin "3") (pinfunction "OUT1_3") (pintype "bidirectional"))
    )
    (net (code "95") (name "unconnected-(U$8-OUT2-Pad8)") (class "Default")
      (node (ref "U$8") (pin "8") (pinfunction "OUT2_8") (pintype "bidirectional"))
    )
    (net (code "96") (name "unconnected-(U$8-OUT3-Pad13)") (class "Default")
      (node (ref "U$8") (pin "13") (pinfunction "OUT3_13") (pintype "bidirectional"))
    )
    (net (code "97") (name "unconnected-(U$10-PGOOD1-Pad4)") (class "Default")
      (node (ref "U$10") (pin "4") (pinfunction "PGOOD1_4") (pintype "bidirectional"))
    )
    (net (code "98") (name "unconnected-(U$10-PGOOD2-Pad11)") (class "Default")
      (node (ref "U$10") (pin "11") (pinfunction "PGOOD2_11") (pintype "bidirectional"))
    )
    (net (code "99") (name "unconnected-(U$10-TRACKSS1-Pad2)") (class "Default")
      (node (ref "U$10") (pin "2") (pinfunction "TRACKSS1_2") (pintype "bidirectional"))
    )
    (net (code "100") (name "unconnected-(U$10-TRACKSS2-Pad13)") (class "Default")
      (node (ref "U$10") (pin "13") (pinfunction "TRACKSS2_13") (pintype "bidirectional"))
    )
    (net (code "101") (name "unconnected-(U$10-_SW1-Pad27)") (class "Default")
      (node (ref "U$10") (pin "27") (pinfunction "_SW1_27") (pintype "bidirectional"))
    )
    (net (code "102") (name "unconnected-(U$10-_SW2-Pad17)") (class "Default")
      (node (ref "U$10") (pin "17") (pinfunction "_SW2_17") (pintype "bidirectional"))
    )
    (net (code "103") (name "unconnected-(U$10-_VIN1-Pad25)") (class "Default")
      (node (ref "U$10") (pin "25") (pinfunction "_VIN1_25") (pintype "bidirectional"))
    )
    (net (code "104") (name "unconnected-(U$10-_VIN2-Pad19)") (class "Default")
      (node (ref "U$10") (pin "19") (pinfunction "_VIN2_19") (pintype "bidirectional"))
    )
    (net (code "105") (name "unconnected-(U$13-CLK-Pad20)") (class "Default")
      (node (ref "U$13") (pin "20") (pinfunction "CLK_20") (pintype "bidirectional"))
    )
    (net (code "106") (name "unconnected-(U$13-CMD-Pad19)") (class "Default")
      (node (ref "U$13") (pin "19") (pinfunction "CMD_19") (pintype "bidirectional"))
    )
    (net (code "107") (name "unconnected-(U$13-SD0-Pad21)") (class "Default")
      (node (ref "U$13") (pin "21") (pinfunction "SD0_21") (pintype "bidirectional"))
    )
    (net (code "108") (name "unconnected-(U$13-SD1-Pad22)") (class "Default")
      (node (ref "U$13") (pin "22") (pinfunction "SD1_22") (pintype "bidirectional"))
    )
    (net (code "109") (name "unconnected-(U$13-SD2-Pad17)") (class "Default")
      (node (ref "U$13") (pin "17") (pinfunction "SD2_17") (pintype "bidirectional"))
    )
    (net (code "110") (name "unconnected-(U$13-SD3-Pad18)") (class "Default")
      (node (ref "U$13") (pin "18") (pinfunction "SD3_18") (pintype "bidirectional"))
    )
    (net (code "111") (name "unconnected-(U$18-Q0-Pad15)") (class "Default")
      (node (ref "U$18") (pin "15") (pinfunction "Q0_15") (pintype "bidirectional"))
    )
    (net (code "112") (name "unconnected-(U$20-Q7S-Pad9)") (class "Default")
      (node (ref "U$20") (pin "9") (pinfunction "Q7S_9") (pintype "bidirectional"))
    )
    (net (code "113") (name "unconnected-(U1-PA1{slash}USART2_RTS-Pad15)") (class "Default")
      (node (ref "U1") (pin "15") (pinfunction "PA1/USART2_RTS_15") (pintype "bidirectional"))
    )
    (net (code "114") (name "unconnected-(U1-PA4{slash}USART2_CK-Pad20)") (class "Default")
      (node (ref "U1") (pin "20") (pinfunction "PA4/USART2_CK_20") (pintype "bidirectional"))
    )
    (net (code "115") (name "unconnected-(U1-PA5{slash}SPI1_SCK-Pad21)") (class "Default")
      (node (ref "U1") (pin "21") (pinfunction "PA5/SPI1_SCK_21") (pintype "bidirectional"))
    )
    (net (code "116") (name "unconnected-(U1-PA8-Pad41)") (class "Default")
      (node (ref "U1") (pin "41") (pinfunction "PA8_41") (pintype "bidirectional"))
    )
    (net (code "117") (name "unconnected-(U1-PA11-Pad44)") (class "Default")
      (node (ref "U1") (pin "44") (pinfunction "PA11_44") (pintype "bidirectional"))
    )
    (net (code "118") (name "unconnected-(U1-PA12-Pad45)") (class "Default")
      (node (ref "U1") (pin "45") (pinfunction "PA12_45") (pintype "bidirectional"))
    )
    (net (code "119") (name "unconnected-(U1-PA15-Pad50)") (class "Default")
      (node (ref "U1") (pin "50") (pinfunction "PA15_50") (pintype "bidirectional"))
    )
    (net (code "120") (name "unconnected-(U1-PB0-Pad26)") (class "Default")
      (node (ref "U1") (pin "26") (pinfunction "PB0_26") (pintype "bidirectional"))
    )
    (net (code "121") (name "unconnected-(U1-PB1-Pad27)") (class "Default")
      (node (ref "U1") (pin "27") (pinfunction "PB1_27") (pintype "bidirectional"))
    )
    (net (code "122") (name "unconnected-(U1-PB3-Pad55)") (class "Default")
      (node (ref "U1") (pin "55") (pinfunction "PB3_55") (pintype "bidirectional"))
    )
    (net (code "123") (name "unconnected-(U1-PB4-Pad56)") (class "Default")
      (node (ref "U1") (pin "56") (pinfunction "PB4_56") (pintype "bidirectional"))
    )
    (net (code "124") (name "unconnected-(U1-PB5-Pad57)") (class "Default")
      (node (ref "U1") (pin "57") (pinfunction "PB5_57") (pintype "bidirectional"))
    )
    (net (code "125") (name "unconnected-(U1-PB8-Pad61)") (class "Default")
      (node (ref "U1") (pin "61") (pinfunction "PB8_61") (pintype "bidirectional"))
    )
    (net (code "126") (name "unconnected-(U1-PB12-Pad33)") (class "Default")
      (node (ref "U1") (pin "33") (pinfunction "PB12_33") (pintype "bidirectional"))
    )
    (net (code "127") (name "unconnected-(U1-PB13-Pad34)") (class "Default")
      (node (ref "U1") (pin "34") (pinfunction "PB13_34") (pintype "bidirectional"))
    )
    (net (code "128") (name "unconnected-(U1-PB14-Pad35)") (class "Default")
      (node (ref "U1") (pin "35") (pinfunction "PB14_35") (pintype "bidirectional"))
    )
    (net (code "129") (name "unconnected-(U1-PB15-Pad36)") (class "Default")
      (node (ref "U1") (pin "36") (pinfunction "PB15_36") (pintype "bidirectional"))
    )
    (net (code "130") (name "unconnected-(U1-PC0-Pad8)") (class "Default")
      (node (ref "U1") (pin "8") (pinfunction "PC0_8") (pintype "bidirectional"))
    )
    (net (code "131") (name "unconnected-(U1-PC1-Pad9)") (class "Default")
      (node (ref "U1") (pin "9") (pinfunction "PC1_9") (pintype "bidirectional"))
    )
    (net (code "132") (name "unconnected-(U1-PC2{slash}SPI2_MISO-Pad10)") (class "Default")
      (node (ref "U1") (pin "10") (pinfunction "PC2/SPI2_MISO_10") (pintype "bidirectional"))
    )
    (net (code "133") (name "unconnected-(U1-PC3{slash}SPI2_MOSI-Pad11)") (class "Default")
      (node (ref "U1") (pin "11") (pinfunction "PC3/SPI2_MOSI_11") (pintype "bidirectional"))
    )
    (net (code "134") (name "unconnected-(U1-PC4-Pad24)") (class "Default")
      (node (ref "U1") (pin "24") (pinfunction "PC4_24") (pintype "bidirectional"))
    )
    (net (code "135") (name "unconnected-(U1-PC5-Pad25)") (class "Default")
      (node (ref "U1") (pin "25") (pinfunction "PC5_25") (pintype "bidirectional"))
    )
    (net (code "136") (name "unconnected-(U1-PC6-Pad37)") (class "Default")
      (node (ref "U1") (pin "37") (pinfunction "PC6_37") (pintype "bidirectional"))
    )
    (net (code "137") (name "unconnected-(U1-PC7-Pad38)") (class "Default")
      (node (ref "U1") (pin "38") (pinfunction "PC7_38") (pintype "bidirectional"))
    )
    (net (code "138") (name "unconnected-(U1-PC8-Pad39)") (class "Default")
      (node (ref "U1") (pin "39") (pinfunction "PC8_39") (pintype "bidirectional"))
    )
    (net (code "139") (name "unconnected-(U1-PC9-Pad40)") (class "Default")
      (node (ref "U1") (pin "40") (pinfunction "PC9_40") (pintype "bidirectional"))
    )
    (net (code "140") (name "unconnected-(U1-PC13{slash}RTC_OUT-Pad2)") (class "Default")
      (node (ref "U1") (pin "2") (pinfunction "PC13/RTC_OUT_2") (pintype "bidirectional"))
    )
  )
)
